# easyeda.net
KiCad netlist of a schematic drawn in EasyEDA
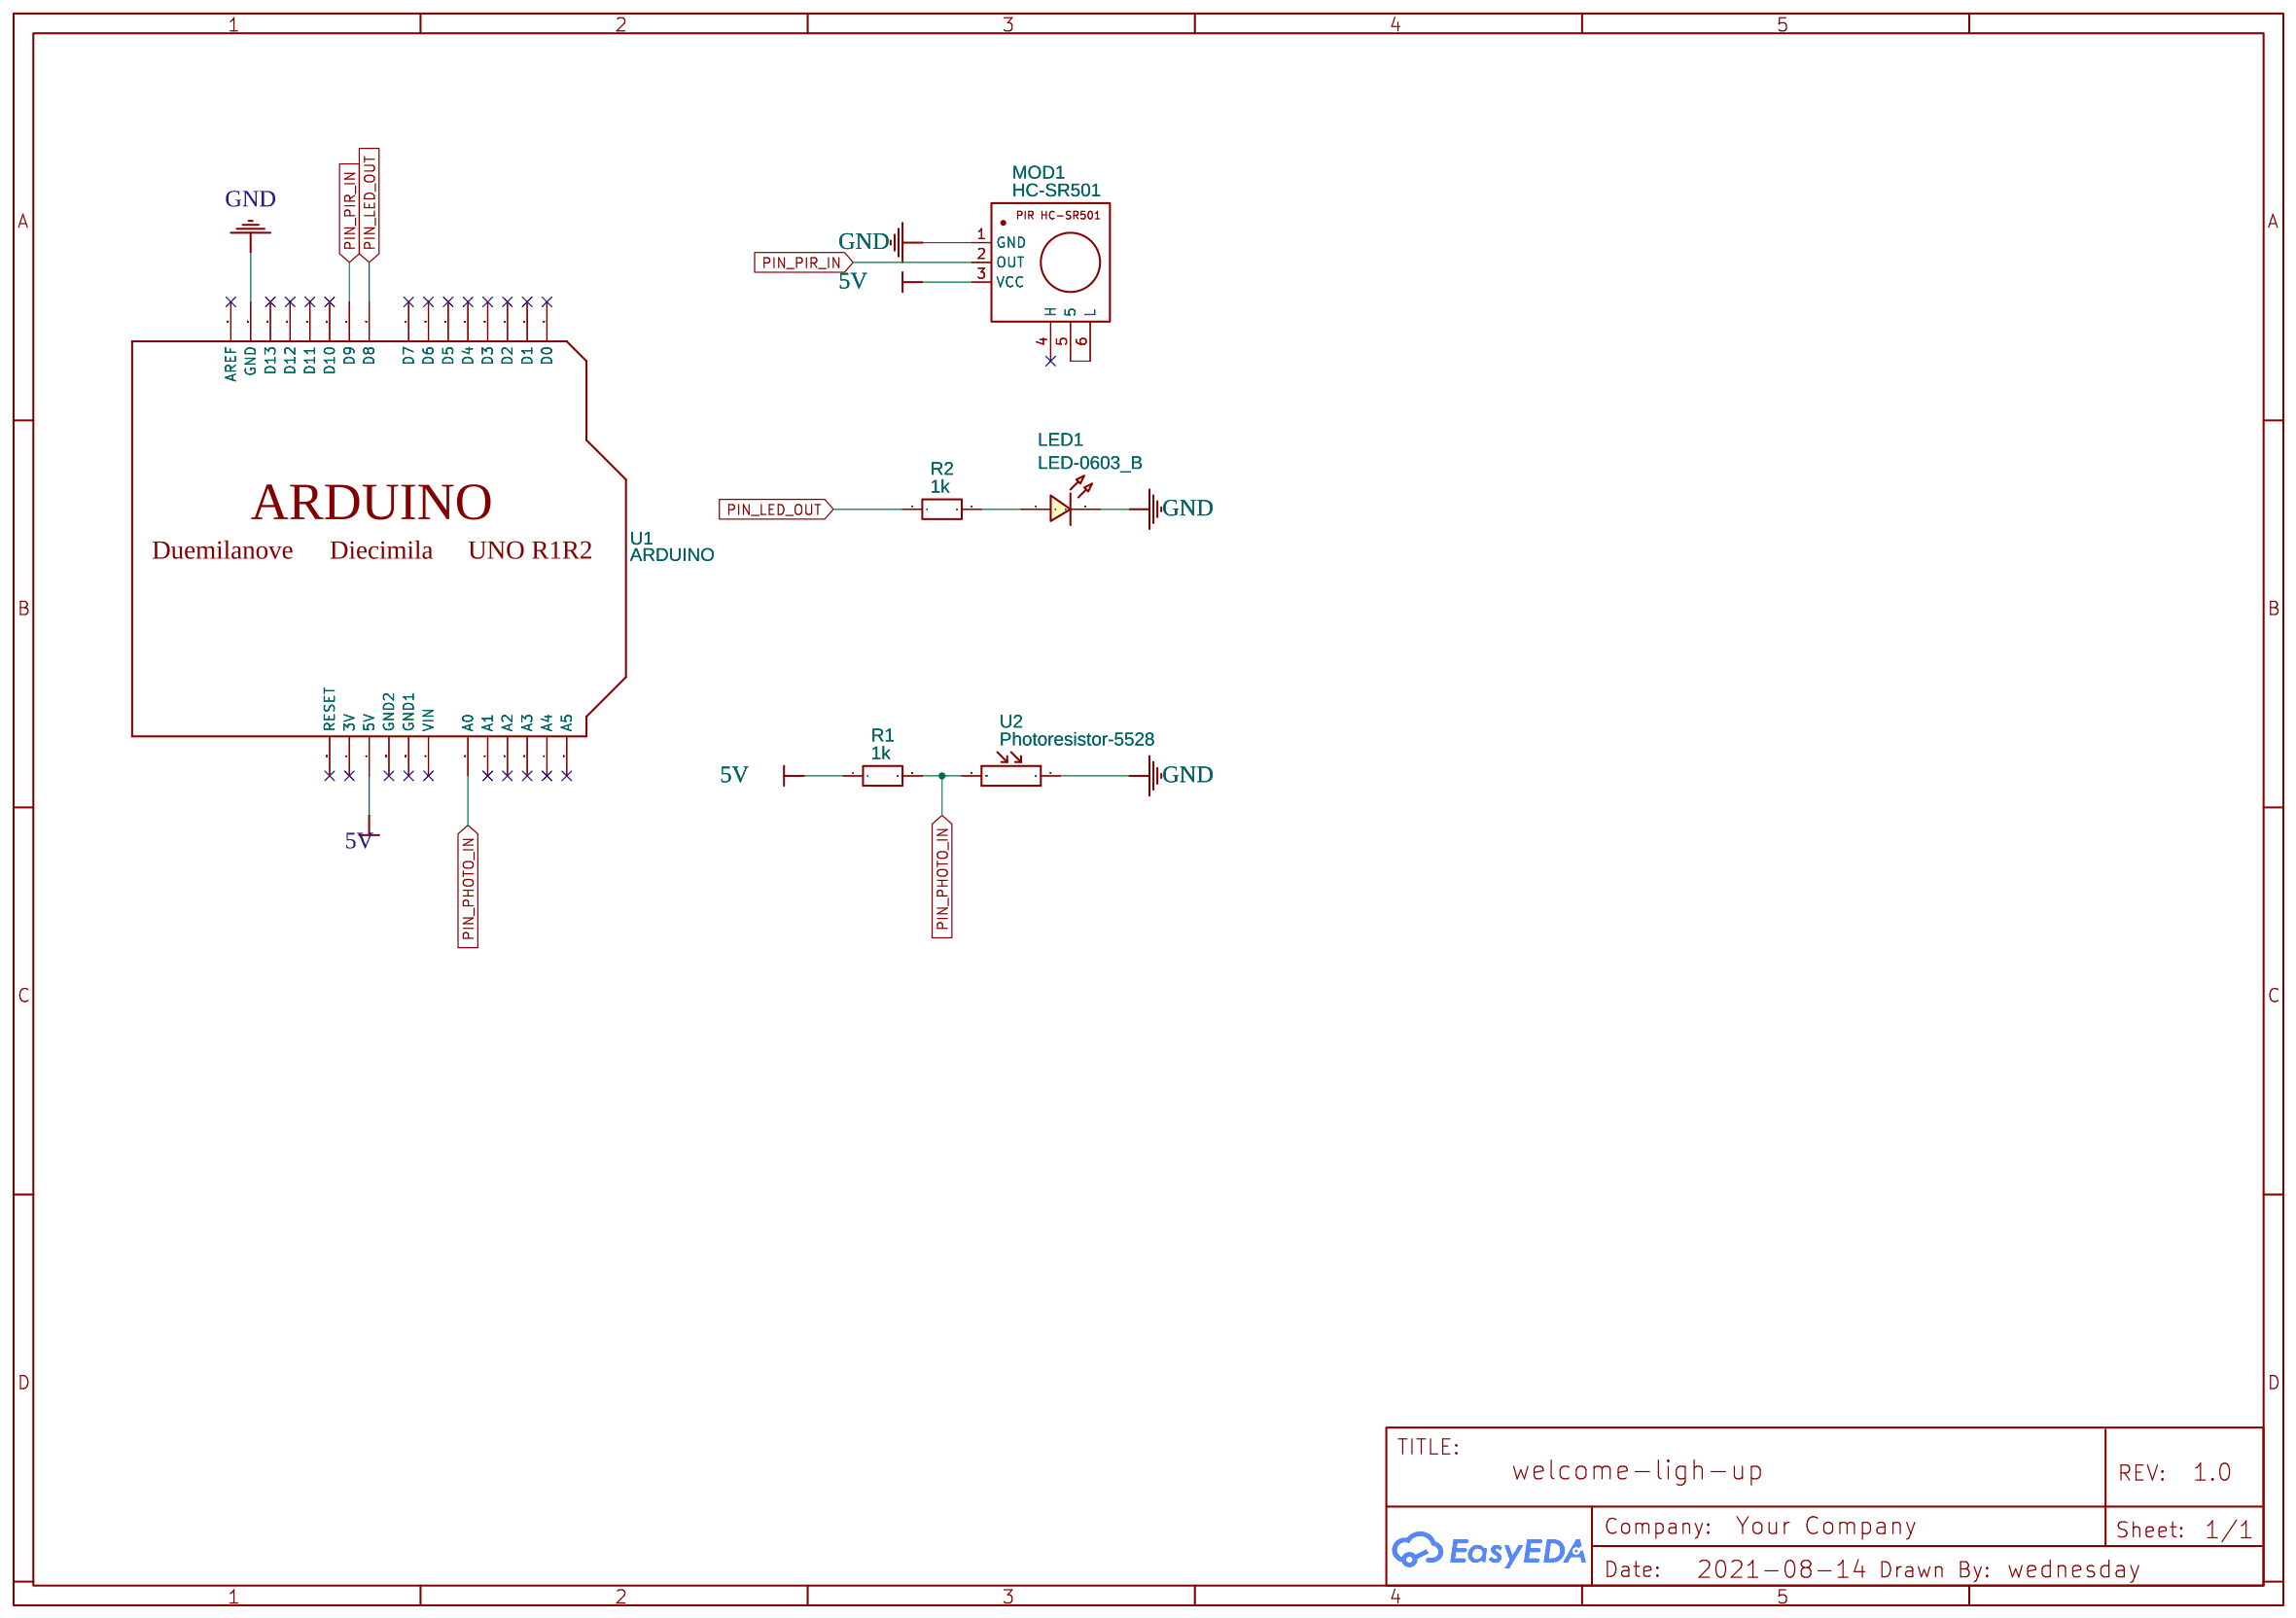
[diagram p0: schematic sheet]

(export (version "E")
  (design (tool "Eeschema 10.0.6"))
  (components
    (comp (ref "LED1")
      (value "LED-0603_B")
      (fields
        (field (name "BOM_Manufacturer Part") "19-217/BHC-ZL1M2RY/3T")
        (field (name "BOM_Supplier Part") "C72041")
      )
      (libsource (lib "") (part "LED-0603_B"))
    )
    (comp (ref "MOD1")
      (value "HC-SR501")
      (fields
        (field (name "BOM_Manufacturer Part") "PIR SR502")
        (field (name "BOM_Supplier Part") "PIR MODULE SR502")
      )
      (libsource (lib "") (part "HC-SR501"))
    )
    (comp (ref "R1") (value "1k") (libsource (lib "") (part "R_0603_EU")))
    (comp (ref "R2") (value "1k") (libsource (lib "") (part "R_0603_EU")))
    (comp (ref "U1") (value "ARDUINO") (libsource (lib "") (part "ARDUINO")))
    (comp (ref "U2") (value "Photoresistor-5528") (libsource (lib "") (part "Photoresistor-5528")))
  )
  (nets
    (net (code "1") (name "5V") (class "Default")
      (node (ref "MOD1") (pin "3") (pinfunction "VCC_3") (pintype "unspecified"))
      (node (ref "R1") (pin "1") (pinfunction "1_1") (pintype "unspecified"))
      (node (ref "U1") (pin "5V") (pinfunction "5V_5V") (pintype "passive"))
    )
    (net (code "2") (name "GND") (class "Default")
      (node (ref "LED1") (pin "2") (pinfunction "2_2") (pintype "unspecified"))
      (node (ref "MOD1") (pin "1") (pinfunction "GND_1") (pintype "unspecified"))
      (node (ref "U1") (pin "GND") (pinfunction "GND_GND") (pintype "passive"))
      (node (ref "U2") (pin "2") (pinfunction "P$2_2") (pintype "unspecified"))
    )
    (net (code "3") (name "Net-(LED1-Pad1)") (class "Default")
      (node (ref "LED1") (pin "1") (pinfunction "1_1") (pintype "unspecified"))
      (node (ref "R2") (pin "2") (pinfunction "2_2") (pintype "unspecified"))
    )
    (net (code "4") (name "Net-(MOD1-L)") (class "Default")
      (node (ref "MOD1") (pin "5") (pinfunction "5_5") (pintype "unspecified"))
      (node (ref "MOD1") (pin "6") (pinfunction "L_6") (pintype "unspecified"))
    )
    (net (code "5") (name "PIN_LED_OUT") (class "Default")
      (node (ref "R2") (pin "1") (pinfunction "1_1") (pintype "unspecified"))
      (node (ref "U1") (pin "D8") (pinfunction "D8_D8") (pintype "unspecified"))
    )
    (net (code "6") (name "PIN_PHOTO_IN") (class "Default")
      (node (ref "R1") (pin "2") (pinfunction "2_2") (pintype "unspecified"))
      (node (ref "U1") (pin "A0") (pinfunction "A0_A0") (pintype "unspecified"))
      (node (ref "U2") (pin "1") (pinfunction "P$1_1") (pintype "unspecified"))
    )
    (net (code "7") (name "PIN_PIR_IN") (class "Default")
      (node (ref "MOD1") (pin "2") (pinfunction "OUT_2") (pintype "unspecified"))
      (node (ref "U1") (pin "D9") (pinfunction "D9_D9") (pintype "unspecified"))
    )
    (net (code "8") (name "unconnected-(MOD1-H-Pad4)") (class "Default")
      (node (ref "MOD1") (pin "4") (pinfunction "H_4") (pintype "unspecified+no_connect"))
    )
    (net (code "9") (name "unconnected-(U1-Pad3V)") (class "Default")
      (node (ref "U1") (pin "3V") (pinfunction "3V_3V") (pintype "passive+no_connect"))
    )
    (net (code "10") (name "unconnected-(U1-PadA1)") (class "Default")
      (node (ref "U1") (pin "A1") (pinfunction "A1_A1") (pintype "unspecified+no_connect"))
    )
    (net (code "11") (name "unconnected-(U1-PadA2)") (class "Default")
      (node (ref "U1") (pin "A2") (pinfunction "A2_A2") (pintype "unspecified+no_connect"))
    )
    (net (code "12") (name "unconnected-(U1-PadA3)") (class "Default")
      (node (ref "U1") (pin "A3") (pinfunction "A3_A3") (pintype "unspecified+no_connect"))
    )
    (net (code "13") (name "unconnected-(U1-PadA4)") (class "Default")
      (node (ref "U1") (pin "A4") (pinfunction "A4_A4") (pintype "unspecified+no_connect"))
    )
    (net (code "14") (name "unconnected-(U1-PadA5)") (class "Default")
      (node (ref "U1") (pin "A5") (pinfunction "A5_A5") (pintype "unspecified+no_connect"))
    )
    (net (code "15") (name "unconnected-(U1-PadAREF)") (class "Default")
      (node (ref "U1") (pin "AREF") (pinfunction "AREF_AREF") (pintype "unspecified+no_connect"))
    )
    (net (code "16") (name "unconnected-(U1-PadD0)") (class "Default")
      (node (ref "U1") (pin "D0") (pinfunction "D0_D0") (pintype "unspecified+no_connect"))
    )
    (net (code "17") (name "unconnected-(U1-PadD1)") (class "Default")
      (node (ref "U1") (pin "D1") (pinfunction "D1_D1") (pintype "unspecified+no_connect"))
    )
    (net (code "18") (name "unconnected-(U1-PadD2)") (class "Default")
      (node (ref "U1") (pin "D2") (pinfunction "D2_D2") (pintype "unspecified+no_connect"))
    )
    (net (code "19") (name "unconnected-(U1-PadD3)") (class "Default")
      (node (ref "U1") (pin "D3") (pinfunction "D3_D3") (pintype "unspecified+no_connect"))
    )
    (net (code "20") (name "unconnected-(U1-PadD4)") (class "Default")
      (node (ref "U1") (pin "D4") (pinfunction "D4_D4") (pintype "unspecified+no_connect"))
    )
    (net (code "21") (name "unconnected-(U1-PadD5)") (class "Default")
      (node (ref "U1") (pin "D5") (pinfunction "D5_D5") (pintype "unspecified+no_connect"))
    )
    (net (code "22") (name "unconnected-(U1-PadD6)") (class "Default")
      (node (ref "U1") (pin "D6") (pinfunction "D6_D6") (pintype "unspecified+no_connect"))
    )
    (net (code "23") (name "unconnected-(U1-PadD7)") (class "Default")
      (node (ref "U1") (pin "D7") (pinfunction "D7_D7") (pintype "unspecified+no_connect"))
    )
    (net (code "24") (name "unconnected-(U1-PadD10)") (class "Default")
      (node (ref "U1") (pin "D10") (pinfunction "D10_D10") (pintype "unspecified+no_connect"))
    )
    (net (code "25") (name "unconnected-(U1-PadD11)") (class "Default")
      (node (ref "U1") (pin "D11") (pinfunction "D11_D11") (pintype "unspecified+no_connect"))
    )
    (net (code "26") (name "unconnected-(U1-PadD12)") (class "Default")
      (node (ref "U1") (pin "D12") (pinfunction "D12_D12") (pintype "unspecified+no_connect"))
    )
    (net (code "27") (name "unconnected-(U1-PadD13)") (class "Default")
      (node (ref "U1") (pin "D13") (pinfunction "D13_D13") (pintype "unspecified+no_connect"))
    )
    (net (code "28") (name "unconnected-(U1-PadGND1)") (class "Default")
      (node (ref "U1") (pin "GND1") (pinfunction "GND1_GND1") (pintype "passive+no_connect"))
    )
    (net (code "29") (name "unconnected-(U1-PadGND2)") (class "Default")
      (node (ref "U1") (pin "GND2") (pinfunction "GND2_GND2") (pintype "passive+no_connect"))
    )
    (net (code "30") (name "unconnected-(U1-PadRESET)") (class "Default")
      (node (ref "U1") (pin "RESET") (pinfunction "RESET_RESET") (pintype "unspecified+no_connect"))
    )
    (net (code "31") (name "unconnected-(U1-PadVIN)") (class "Default")
      (node (ref "U1") (pin "VIN") (pinfunction "VIN_VIN") (pintype "passive+no_connect"))
    )
  )
)
